# I2C_Keypad.net
KiCad netlist of a schematic drawn in Altium Designer
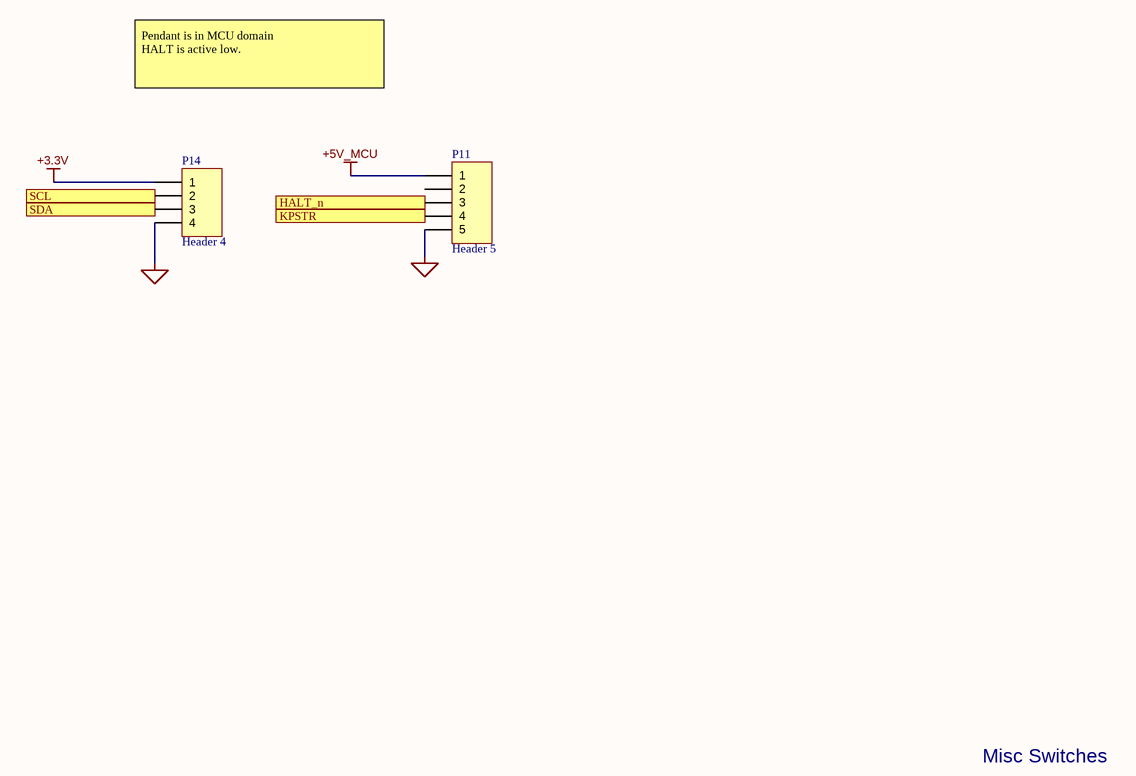
[diagram p0: I2C_Keypad.SchDoc]

(export (version "E")
  (design (tool "Eeschema 10.0.6"))
  (components
    (comp (ref "P11")
      (value "Header 5")
      (footprint "HDR1X5")
      (description "Header, 5-Pin")
      (fields (field (name "PUBLISHER") "Altium Limited"))
      (libsource (lib "PrintNC_GRBLHAL_Breakout") (part "Header 5"))
    )
    (comp (ref "P14")
      (value "Header 4")
      (footprint "HDR1X4")
      (description "Header, 4-Pin")
      (fields (field (name "PUBLISHER") "Altium Limited"))
      (libsource (lib "PrintNC_GRBLHAL_Breakout") (part "Header 4"))
    )
  )
  (nets
    (net (code "1") (name "+3.3V") (class "Default")
      (node (ref "P14") (pin "1") (pinfunction "1_1") (pintype "passive"))
    )
    (net (code "2") (name "+5V_MCU") (class "Default")
      (node (ref "P11") (pin "1") (pinfunction "1_1") (pintype "passive"))
    )
    (net (code "3") (name "/HALT_n") (class "Default")
      (node (ref "P11") (pin "3") (pinfunction "3_3") (pintype "passive"))
    )
    (net (code "4") (name "/KPSTR") (class "Default")
      (node (ref "P11") (pin "4") (pinfunction "4_4") (pintype "passive"))
    )
    (net (code "5") (name "/SCL") (class "Default")
      (node (ref "P14") (pin "2") (pinfunction "2_2") (pintype "passive"))
    )
    (net (code "6") (name "/SDA") (class "Default")
      (node (ref "P14") (pin "3") (pinfunction "3_3") (pintype "passive"))
    )
    (net (code "7") (name "MCU_GND") (class "Default")
      (node (ref "P11") (pin "5") (pinfunction "5_5") (pintype "passive"))
      (node (ref "P14") (pin "4") (pinfunction "4_4") (pintype "passive"))
    )
    (net (code "8") (name "unconnected-(P11-Pad2)") (class "Default")
      (node (ref "P11") (pin "2") (pinfunction "2_2") (pintype "passive"))
    )
  )
)
